# PWMDriver.net
KiCad netlist of a schematic drawn in Altium Designer
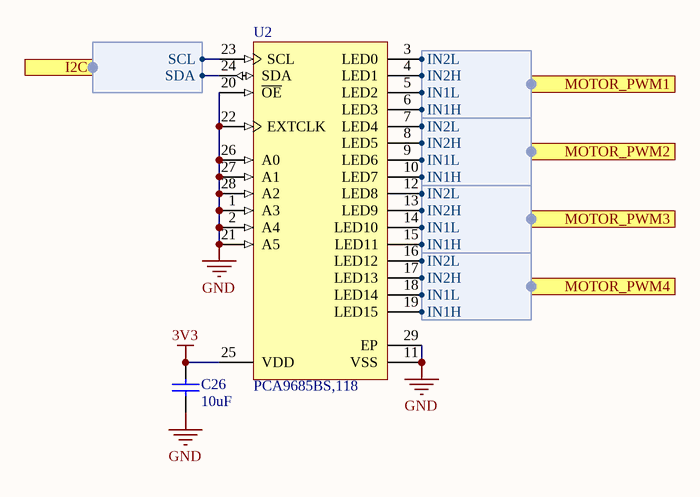
[diagram p0: PWMDriver.SchDoc]

(export (version "E")
  (design (tool "Eeschema 10.0.6"))
  (components
    (comp (ref "C26")
      (value "10uF")
      (footprint "C0402[1005X55]")
      (description "10uF 6.3V 20% 0402 (1005 Metric)")
      (fields (field (name "PARTNUMBER") "GRM155R60J106ME44D") (field (name "MANUFACTURER") "Murata"))
      (libsource (lib "Capacitors") (part "CAP_10uF_6.3V_0402_20%"))
    )
    (comp (ref "U2")
      (value "PCA9685BS,118")
      (footprint "VQFN-28")
      (description "IC LED DRVR LIN DIM 25MA 28HVQFN")
      (fields (field (name "MANUFACTURER") "NXP"))
      (libsource (lib "ICs") (part "PCA9685BS,118"))
    )
  )
  (nets
    (net (code "3") (name "/SCL") (class "Default")
      (node (ref "U2") (pin "23") (pinfunction "SCL_23") (pintype "input"))
    )
    (net (code "4") (name "/SDA") (class "Default")
      (node (ref "U2") (pin "24") (pinfunction "SDA_24") (pintype "bidirectional"))
    )
    (net (code "7") (name "3V3") (class "Default")
      (node (ref "C26") (pin "2") (pinfunction "2_2") (pintype "passive"))
      (node (ref "U2") (pin "25") (pinfunction "VDD_25") (pintype "power_in"))
    )
    (net (code "8") (name "GND") (class "Default")
      (node (ref "C26") (pin "1") (pinfunction "1_1") (pintype "passive"))
      (node (ref "U2") (pin "1") (pinfunction "A3_1") (pintype "input"))
      (node (ref "U2") (pin "11") (pinfunction "VSS_11") (pintype "power_in"))
      (node (ref "U2") (pin "2") (pinfunction "A4_2") (pintype "input"))
      (node (ref "U2") (pin "20") (pinfunction "~{OE}_20") (pintype "input"))
      (node (ref "U2") (pin "21") (pinfunction "A5_21") (pintype "input"))
      (node (ref "U2") (pin "22") (pinfunction "EXTCLK_22") (pintype "input"))
      (node (ref "U2") (pin "26") (pinfunction "A0_26") (pintype "input"))
      (node (ref "U2") (pin "27") (pinfunction "A1_27") (pintype "input"))
      (node (ref "U2") (pin "28") (pinfunction "A2_28") (pintype "input"))
      (node (ref "U2") (pin "29") (pinfunction "EP_29") (pintype "power_in"))
    )
    (net (code "9") (name "unconnected-(U2-LED0-Pad3)") (class "Default")
      (node (ref "U2") (pin "3") (pinfunction "LED0_3") (pintype "tri_state"))
    )
    (net (code "10") (name "unconnected-(U2-LED1-Pad4)") (class "Default")
      (node (ref "U2") (pin "4") (pinfunction "LED1_4") (pintype "tri_state"))
    )
    (net (code "11") (name "unconnected-(U2-LED2-Pad5)") (class "Default")
      (node (ref "U2") (pin "5") (pinfunction "LED2_5") (pintype "tri_state"))
    )
    (net (code "12") (name "unconnected-(U2-LED3-Pad6)") (class "Default")
      (node (ref "U2") (pin "6") (pinfunction "LED3_6") (pintype "tri_state"))
    )
    (net (code "13") (name "unconnected-(U2-LED4-Pad7)") (class "Default")
      (node (ref "U2") (pin "7") (pinfunction "LED4_7") (pintype "tri_state"))
    )
    (net (code "14") (name "unconnected-(U2-LED5-Pad8)") (class "Default")
      (node (ref "U2") (pin "8") (pinfunction "LED5_8") (pintype "tri_state"))
    )
    (net (code "15") (name "unconnected-(U2-LED6-Pad9)") (class "Default")
      (node (ref "U2") (pin "9") (pinfunction "LED6_9") (pintype "tri_state"))
    )
    (net (code "16") (name "unconnected-(U2-LED7-Pad10)") (class "Default")
      (node (ref "U2") (pin "10") (pinfunction "LED7_10") (pintype "tri_state"))
    )
    (net (code "17") (name "unconnected-(U2-LED8-Pad12)") (class "Default")
      (node (ref "U2") (pin "12") (pinfunction "LED8_12") (pintype "tri_state"))
    )
    (net (code "18") (name "unconnected-(U2-LED9-Pad13)") (class "Default")
      (node (ref "U2") (pin "13") (pinfunction "LED9_13") (pintype "tri_state"))
    )
    (net (code "19") (name "unconnected-(U2-LED10-Pad14)") (class "Default")
      (node (ref "U2") (pin "14") (pinfunction "LED10_14") (pintype "tri_state"))
    )
    (net (code "20") (name "unconnected-(U2-LED11-Pad15)") (class "Default")
      (node (ref "U2") (pin "15") (pinfunction "LED11_15") (pintype "tri_state"))
    )
    (net (code "21") (name "unconnected-(U2-LED12-Pad16)") (class "Default")
      (node (ref "U2") (pin "16") (pinfunction "LED12_16") (pintype "tri_state"))
    )
    (net (code "22") (name "unconnected-(U2-LED13-Pad17)") (class "Default")
      (node (ref "U2") (pin "17") (pinfunction "LED13_17") (pintype "tri_state"))
    )
    (net (code "23") (name "unconnected-(U2-LED14-Pad18)") (class "Default")
      (node (ref "U2") (pin "18") (pinfunction "LED14_18") (pintype "tri_state"))
    )
    (net (code "24") (name "unconnected-(U2-LED15-Pad19)") (class "Default")
      (node (ref "U2") (pin "19") (pinfunction "LED15_19") (pintype "tri_state"))
    )
  )
)
